# schematic.net
KiCad netlist of a schematic drawn in EAGLE
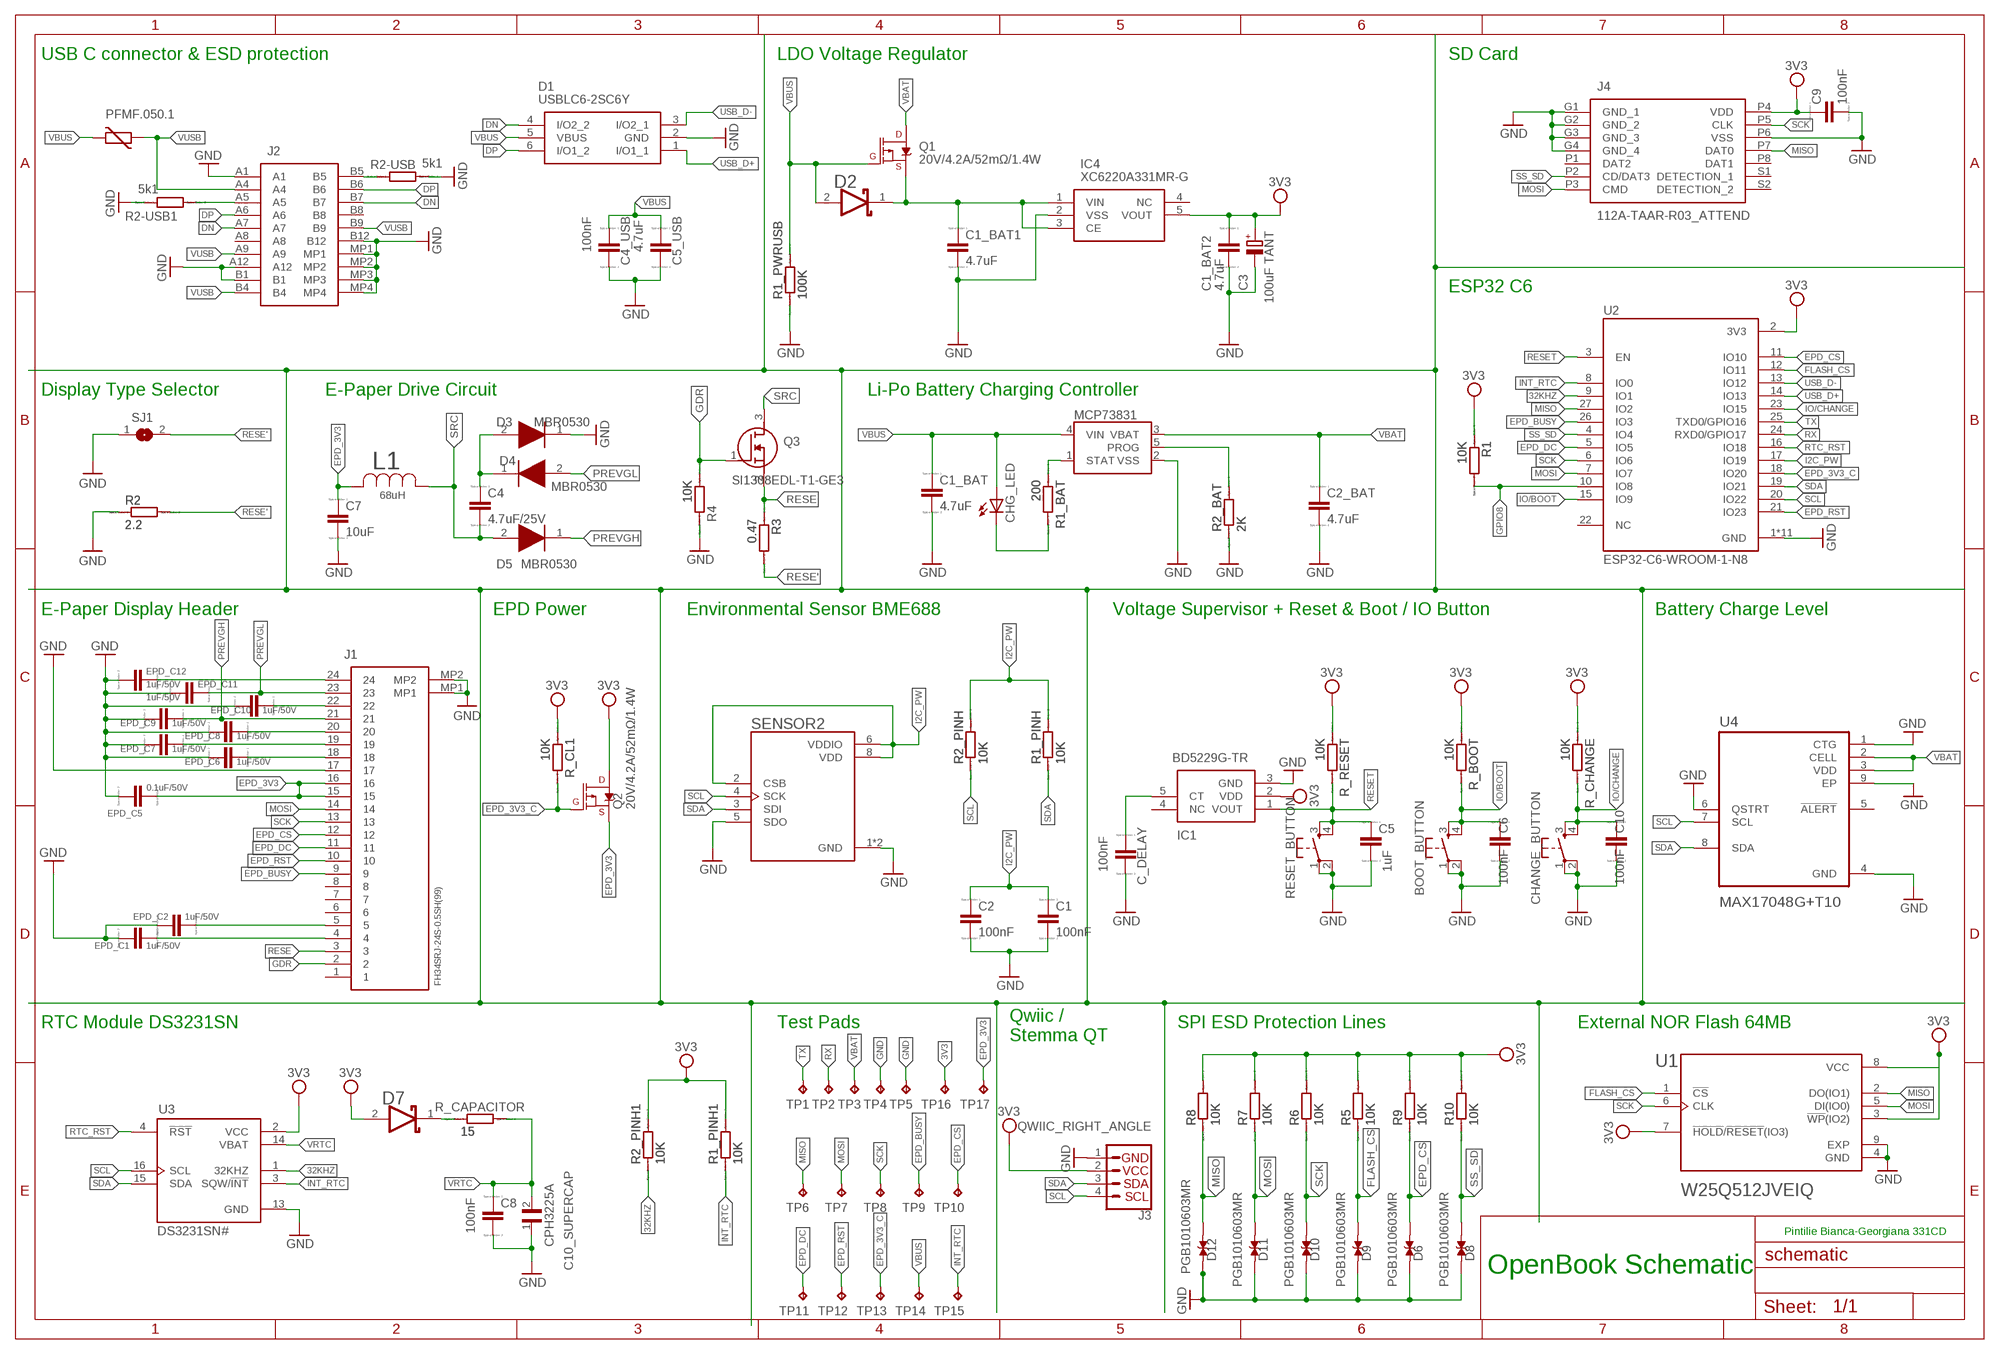
[diagram p0: schematic, sheet 1]

(export (version "E")
  (design (tool "Eeschema 10.0.6"))
  (components
    (comp (ref "BOOT_BUTTON")
      (value "BUTTON_CUSYOMV1")
      (footprint "eagle-import:MYBUTTON")
      (libsource (lib "eagle-import") (part "BUTTON_CUSYOMV1"))
    )
    (comp (ref "C1")
      (value "100nF")
      (footprint "eagle-import:EAGLE-LTSPICE_C0402")
      (libsource (lib "eagle-import") (part "EAGLE-LTSPICE_CC0402"))
    )
    (comp (ref "C1_BAT")
      (value "4.7uF")
      (footprint "eagle-import:EAGLE-LTSPICE_C0402")
      (libsource (lib "eagle-import") (part "EAGLE-LTSPICE_CC0402"))
    )
    (comp (ref "C1_BAT1")
      (value "4.7uF")
      (footprint "eagle-import:EAGLE-LTSPICE_C0402")
      (libsource (lib "eagle-import") (part "EAGLE-LTSPICE_CC0402"))
    )
    (comp (ref "C1_BAT2")
      (value "4.7uF")
      (footprint "eagle-import:EAGLE-LTSPICE_C0402")
      (libsource (lib "eagle-import") (part "EAGLE-LTSPICE_CC0402"))
    )
    (comp (ref "C2")
      (value "100nF")
      (footprint "eagle-import:EAGLE-LTSPICE_C0402")
      (libsource (lib "eagle-import") (part "EAGLE-LTSPICE_CC0402"))
    )
    (comp (ref "C2_BAT")
      (value "4.7uF")
      (footprint "eagle-import:EAGLE-LTSPICE_C0402")
      (libsource (lib "eagle-import") (part "EAGLE-LTSPICE_CC0402"))
    )
    (comp (ref "C3")
      (value "100uF TANT")
      (footprint "eagle-import:RCL_CT3528")
      (libsource (lib "eagle-import") (part "RCL_CPOL-EUCT3528"))
    )
    (comp (ref "C4")
      (value "4.7uF/25V")
      (footprint "eagle-import:EAGLE-LTSPICE_C0402")
      (libsource (lib "eagle-import") (part "EAGLE-LTSPICE_CC0402"))
    )
    (comp (ref "C4_USB")
      (value "100nF")
      (footprint "eagle-import:EAGLE-LTSPICE_C0402")
      (libsource (lib "eagle-import") (part "EAGLE-LTSPICE_CC0402"))
    )
    (comp (ref "C5")
      (value "1uF")
      (footprint "eagle-import:EAGLE-LTSPICE_C0402")
      (libsource (lib "eagle-import") (part "EAGLE-LTSPICE_CC0402"))
    )
    (comp (ref "C5_USB")
      (value "4.7uF")
      (footprint "eagle-import:EAGLE-LTSPICE_C0402")
      (libsource (lib "eagle-import") (part "EAGLE-LTSPICE_CC0402"))
    )
    (comp (ref "C6")
      (value "100nF")
      (footprint "eagle-import:EAGLE-LTSPICE_C0402")
      (libsource (lib "eagle-import") (part "EAGLE-LTSPICE_CC0402"))
    )
    (comp (ref "C7")
      (value "10uF")
      (footprint "eagle-import:EAGLE-LTSPICE_C0402")
      (libsource (lib "eagle-import") (part "EAGLE-LTSPICE_CC0402"))
    )
    (comp (ref "C8")
      (value "100nF")
      (footprint "eagle-import:EAGLE-LTSPICE_C0402")
      (libsource (lib "eagle-import") (part "EAGLE-LTSPICE_CC0402"))
    )
    (comp (ref "C9")
      (value "100nF")
      (footprint "eagle-import:EAGLE-LTSPICE_C0402")
      (libsource (lib "eagle-import") (part "EAGLE-LTSPICE_CC0402"))
    )
    (comp (ref "C10")
      (value "100nF")
      (footprint "eagle-import:EAGLE-LTSPICE_C0402")
      (libsource (lib "eagle-import") (part "EAGLE-LTSPICE_CC0402"))
    )
    (comp (ref "C10_SUPERCAP")
      (value "CPH3225A")
      (footprint "eagle-import:CAPCP3225X100N")
      (fields (field (name "MF") "Seiko Instruments"))
      (libsource (lib "eagle-import") (part "CPH3225A"))
    )
    (comp (ref "CHANGE_BUTTON")
      (value "BUTTON_CUSYOMV1")
      (footprint "eagle-import:MYBUTTON")
      (libsource (lib "eagle-import") (part "BUTTON_CUSYOMV1"))
    )
    (comp (ref "CHG_LED")
      (value "ADAFRUIT_LEDCHIP-LED0603")
      (footprint "eagle-import:ADAFRUIT_CHIP-LED0603")
      (libsource (lib "eagle-import") (part "ADAFRUIT_LEDCHIP-LED0603"))
    )
    (comp (ref "C_DELAY")
      (value "100nF")
      (footprint "eagle-import:EAGLE-LTSPICE_C0402")
      (libsource (lib "eagle-import") (part "EAGLE-LTSPICE_CC0402"))
    )
    (comp (ref "D1")
      (value "USBLC6-2SC6Y")
      (footprint "eagle-import:SOT95P280X145-6N")
      (fields (field (name "MF") "STMicroelectronics"))
      (libsource (lib "eagle-import") (part "USBLC6-2SC6Y"))
    )
    (comp (ref "D2")
      (value "ESP32_WROVER_AVX---SD0805S020S1R0_AVX_SD0805S020S1R0_0_0AVX_SD0805S020S1R0_0_0")
      (footprint "eagle-import:ESP32_WROVER_AVX---SD0805S020S1R0_AVX_SD0805S020S1R0_0")
      (fields
        (field (name "DIGIKEY_PART_NUMBER") "478-7800-1-ND")
        (field (name "MF") "AVX")
        (field (name "MOUSER_PART_NUMBER") "581-SD0805S020S1R0")
      )
      (libsource (lib "eagle-import") (part "ESP32_WROVER_AVX---SD0805S020S1R0_AVX_SD0805S020S1R0_0_0AVX_SD0805S020S1R0_0_0"))
    )
    (comp (ref "D3")
      (value "MBR0530")
      (footprint "eagle-import:SOD3716X135N")
      (fields (field (name "MF") "ON Semiconductor"))
      (libsource (lib "eagle-import") (part "MBR0530"))
    )
    (comp (ref "D4")
      (value "MBR0530")
      (footprint "eagle-import:SOD3716X135N")
      (fields (field (name "MF") "ON Semiconductor"))
      (libsource (lib "eagle-import") (part "MBR0530"))
    )
    (comp (ref "D5")
      (value "MBR0530")
      (footprint "eagle-import:SOD3716X135N")
      (fields (field (name "MF") "ON Semiconductor"))
      (libsource (lib "eagle-import") (part "MBR0530"))
    )
    (comp (ref "D6")
      (value "PGB1010603MR")
      (footprint "eagle-import:DIOC1608X36N")
      (fields (field (name "MF") "Littelfuse Inc."))
      (libsource (lib "eagle-import") (part "PGB1010603MR"))
    )
    (comp (ref "D7")
      (value "ESP32_WROVER_AVX---SD0805S020S1R0_AVX_SD0805S020S1R0_0_0AVX_SD0805S020S1R0_0_0")
      (footprint "eagle-import:ESP32_WROVER_AVX---SD0805S020S1R0_AVX_SD0805S020S1R0_0")
      (fields
        (field (name "DIGIKEY_PART_NUMBER") "478-7800-1-ND")
        (field (name "MF") "AVX")
        (field (name "MOUSER_PART_NUMBER") "581-SD0805S020S1R0")
      )
      (libsource (lib "eagle-import") (part "ESP32_WROVER_AVX---SD0805S020S1R0_AVX_SD0805S020S1R0_0_0AVX_SD0805S020S1R0_0_0"))
    )
    (comp (ref "D8")
      (value "PGB1010603MR")
      (footprint "eagle-import:DIOC1608X36N")
      (fields (field (name "MF") "Littelfuse Inc."))
      (libsource (lib "eagle-import") (part "PGB1010603MR"))
    )
    (comp (ref "D9")
      (value "PGB1010603MR")
      (footprint "eagle-import:DIOC1608X36N")
      (fields (field (name "MF") "Littelfuse Inc."))
      (libsource (lib "eagle-import") (part "PGB1010603MR"))
    )
    (comp (ref "D10")
      (value "PGB1010603MR")
      (footprint "eagle-import:DIOC1608X36N")
      (fields (field (name "MF") "Littelfuse Inc."))
      (libsource (lib "eagle-import") (part "PGB1010603MR"))
    )
    (comp (ref "D11")
      (value "PGB1010603MR")
      (footprint "eagle-import:DIOC1608X36N")
      (fields (field (name "MF") "Littelfuse Inc."))
      (libsource (lib "eagle-import") (part "PGB1010603MR"))
    )
    (comp (ref "D12")
      (value "PGB1010603MR")
      (footprint "eagle-import:DIOC1608X36N")
      (fields (field (name "MF") "Littelfuse Inc."))
      (libsource (lib "eagle-import") (part "PGB1010603MR"))
    )
    (comp (ref "EPD_C1")
      (value "1uF/50V")
      (footprint "eagle-import:ESP32_WROVER_EAGLE-LTSPICE_C0402")
      (libsource (lib "eagle-import") (part "ESP32_WROVER_EAGLE-LTSPICE_CC0402"))
    )
    (comp (ref "EPD_C2")
      (value "1uF/50V")
      (footprint "eagle-import:ESP32_WROVER_EAGLE-LTSPICE_C0402")
      (libsource (lib "eagle-import") (part "ESP32_WROVER_EAGLE-LTSPICE_CC0402"))
    )
    (comp (ref "EPD_C5")
      (value "0.1uF/50V")
      (footprint "eagle-import:ESP32_WROVER_EAGLE-LTSPICE_C0402")
      (libsource (lib "eagle-import") (part "ESP32_WROVER_EAGLE-LTSPICE_CC0402"))
    )
    (comp (ref "EPD_C6")
      (value "1uF/50V")
      (footprint "eagle-import:ESP32_WROVER_EAGLE-LTSPICE_C0402")
      (libsource (lib "eagle-import") (part "ESP32_WROVER_EAGLE-LTSPICE_CC0402"))
    )
    (comp (ref "EPD_C7")
      (value "1uF/50V")
      (footprint "eagle-import:ESP32_WROVER_EAGLE-LTSPICE_C0402")
      (libsource (lib "eagle-import") (part "ESP32_WROVER_EAGLE-LTSPICE_CC0402"))
    )
    (comp (ref "EPD_C8")
      (value "1uF/50V")
      (footprint "eagle-import:ESP32_WROVER_EAGLE-LTSPICE_C0402")
      (libsource (lib "eagle-import") (part "ESP32_WROVER_EAGLE-LTSPICE_CC0402"))
    )
    (comp (ref "EPD_C9")
      (value "1uF/50V")
      (footprint "eagle-import:ESP32_WROVER_EAGLE-LTSPICE_C0402")
      (libsource (lib "eagle-import") (part "ESP32_WROVER_EAGLE-LTSPICE_CC0402"))
    )
    (comp (ref "EPD_C10")
      (value "1uF/50V")
      (footprint "eagle-import:ESP32_WROVER_EAGLE-LTSPICE_C0402")
      (fields (field (name "SPICEPREFIX") "EPD_C10"))
      (libsource (lib "eagle-import") (part "ESP32_WROVER_EAGLE-LTSPICE_CC0402"))
    )
    (comp (ref "EPD_C11")
      (value "1uF/50V")
      (footprint "eagle-import:ESP32_WROVER_EAGLE-LTSPICE_C0402")
      (libsource (lib "eagle-import") (part "ESP32_WROVER_EAGLE-LTSPICE_CC0402"))
    )
    (comp (ref "EPD_C12")
      (value "1uF/50V")
      (footprint "eagle-import:ESP32_WROVER_EAGLE-LTSPICE_C0402")
      (libsource (lib "eagle-import") (part "ESP32_WROVER_EAGLE-LTSPICE_CC0402"))
    )
    (comp (ref "IC1")
      (value "BD5229G-TR")
      (footprint "eagle-import:SOT95P280X125-5N")
      (fields (field (name "MOUSER_PART_NUMBER") "755-BD5229G-TR"))
      (libsource (lib "eagle-import") (part "BD5229G-TR"))
    )
    (comp (ref "IC4")
      (value "XC6220A331MR-G")
      (footprint "eagle-import:SOT95P280X120-5N")
      (fields (field (name "MOUSER_PART_NUMBER") "865-XC6220A331MR-G"))
      (libsource (lib "eagle-import") (part "XC6220A331MR-G"))
    )
    (comp (ref "J1")
      (value "FH34SRJ-24S-0.5SH_99_")
      (footprint "eagle-import:FH34SRJ24S05SH99")
      (fields
        (field (name "MANUFACTURER_PART_NUMBER") "FH34SRJ-24S-0.5SH(99)")
        (field (name "MOUSER_PART_NUMBER") "798-FH34SRJ24S05SH99")
      )
      (libsource (lib "eagle-import") (part "FH34SRJ-24S-0.5SH_99_"))
    )
    (comp (ref "J2")
      (value "SAMACSYS_PARTS_USB4110-GF-A")
      (footprint "eagle-import:SAMACSYS_PARTS_USB4110GFA")
      (fields
        (field (name "MANUFACTURER_PART_NUMBER") "USB4110-GF-A")
        (field (name "MOUSER_PART_NUMBER") "640-USB4110-GF-A")
      )
      (libsource (lib "eagle-import") (part "SAMACSYS_PARTS_USB4110-GF-A"))
    )
    (comp (ref "J3")
      (value "QWIIC_RIGHT_ANGLE")
      (footprint "eagle-import:JST04_1MM_RA")
      (libsource (lib "eagle-import") (part "QWIIC_CONNECTORJS-1MM"))
    )
    (comp (ref "J4")
      (value "112A-TAAR-R03_ATTEND")
      (footprint "eagle-import:112ATAARR03ATTEND")
      (fields (field (name "MANUFACTURER_PART_NUMBER") "112A-TAAR-R03 ATTEND"))
      (libsource (lib "eagle-import") (part "112A-TAAR-R03_ATTEND"))
    )
    (comp (ref "L1")
      (value "68uH")
      (footprint "eagle-import:IND_4828-WE-TPC_WRE")
      (fields
        (field (name "MANUFACTURER_PART_NUMBER") "744043680")
        (field (name "COPYRIGHT") "Copyright (C) 2024 Ultra Librarian. All rights reserved.")
      )
      (libsource (lib "eagle-import") (part "744043680IND_4828-WE-TPC_WRE"))
    )
    (comp (ref "MCP73831")
      (value "ESP32_WROVER_SPARKFUN-IC-POWER_MCP73831")
      (footprint "eagle-import:ESP32_WROVER_SPARKFUN-IC-POWER_SOT23-5")
      (libsource (lib "eagle-import") (part "ESP32_WROVER_SPARKFUN-IC-POWER_MCP73831"))
    )
    (comp (ref "PFMF.050.1")
      (value "ESP32C6_VARISTORCN1812")
      (footprint "eagle-import:ESP32C6_VARISTOR_CT_CN1812")
      (libsource (lib "eagle-import") (part "ESP32C6_VARISTORCN1812"))
    )
    (comp (ref "Q1")
      (value "20V/4.2A/52mΩ/1.4W")
      (footprint "eagle-import:ESP32_WROVER_SPARKFUN-DISCRETESEMI_SOT23-3")
      (libsource (lib "eagle-import") (part "ESP32_WROVER_SPARKFUN-DISCRETESEMI_MOSFET_PCH-DMG2305UX-7"))
    )
    (comp (ref "Q2")
      (value "20V/4.2A/52mΩ/1.4W")
      (footprint "eagle-import:ESP32_WROVER_SPARKFUN-DISCRETESEMI_SOT23-3")
      (libsource (lib "eagle-import") (part "ESP32_WROVER_SPARKFUN-DISCRETESEMI_MOSFET_PCH-DMG2305UX-7"))
    )
    (comp (ref "Q3")
      (value "SI1308EDL-T1-GE3")
      (footprint "eagle-import:SOT65P210X110-3N")
      (fields (field (name "MF") "Vishay Siliconix"))
      (libsource (lib "eagle-import") (part "SI1308EDL-T1-GE3"))
    )
    (comp (ref "R1")
      (value "10K")
      (footprint "eagle-import:ESP32_WROVER_EAGLE-LTSPICE_R0402")
      (libsource (lib "eagle-import") (part "ESP32_WROVER_EAGLE-LTSPICE_RR0402"))
    )
    (comp (ref "R1_BAT")
      (value "200")
      (footprint "eagle-import:ESP32_WROVER_EAGLE-LTSPICE_R0402")
      (libsource (lib "eagle-import") (part "ESP32_WROVER_EAGLE-LTSPICE_RR0402"))
    )
    (comp (ref "R1_PINH")
      (value "10K")
      (footprint "eagle-import:ESP32_WROVER_EAGLE-LTSPICE_R0402")
      (libsource (lib "eagle-import") (part "ESP32_WROVER_EAGLE-LTSPICE_RR0402"))
    )
    (comp (ref "R1_PINH1")
      (value "10K")
      (footprint "eagle-import:ESP32_WROVER_EAGLE-LTSPICE_R0402")
      (libsource (lib "eagle-import") (part "ESP32_WROVER_EAGLE-LTSPICE_RR0402"))
    )
    (comp (ref "R1_PWRUSB")
      (value "100K")
      (footprint "eagle-import:ESP32_WROVER_EAGLE-LTSPICE_R0402")
      (libsource (lib "eagle-import") (part "ESP32_WROVER_EAGLE-LTSPICE_RR0402"))
    )
    (comp (ref "R2")
      (value "2.2")
      (footprint "eagle-import:ESP32_WROVER_EAGLE-LTSPICE_R0402")
      (libsource (lib "eagle-import") (part "ESP32_WROVER_EAGLE-LTSPICE_RR0402"))
    )
    (comp (ref "R2-USB")
      (value "5k1")
      (footprint "eagle-import:ESP32_WROVER_EAGLE-LTSPICE_R0402")
      (libsource (lib "eagle-import") (part "ESP32_WROVER_EAGLE-LTSPICE_RR0402"))
    )
    (comp (ref "R2-USB1")
      (value "5k1")
      (footprint "eagle-import:ESP32_WROVER_EAGLE-LTSPICE_R0402")
      (libsource (lib "eagle-import") (part "ESP32_WROVER_EAGLE-LTSPICE_RR0402"))
    )
    (comp (ref "R2_BAT")
      (value "2K")
      (footprint "eagle-import:ESP32_WROVER_EAGLE-LTSPICE_R0402")
      (libsource (lib "eagle-import") (part "ESP32_WROVER_EAGLE-LTSPICE_RR0402"))
    )
    (comp (ref "R2_PINH")
      (value "10K")
      (footprint "eagle-import:ESP32_WROVER_EAGLE-LTSPICE_R0402")
      (libsource (lib "eagle-import") (part "ESP32_WROVER_EAGLE-LTSPICE_RR0402"))
    )
    (comp (ref "R2_PINH1")
      (value "10K")
      (footprint "eagle-import:ESP32_WROVER_EAGLE-LTSPICE_R0402")
      (libsource (lib "eagle-import") (part "ESP32_WROVER_EAGLE-LTSPICE_RR0402"))
    )
    (comp (ref "R3")
      (value "0.47")
      (footprint "eagle-import:ESP32_WROVER_EAGLE-LTSPICE_R0402")
      (libsource (lib "eagle-import") (part "ESP32_WROVER_EAGLE-LTSPICE_RR0402"))
    )
    (comp (ref "R4")
      (value "10K")
      (footprint "eagle-import:ESP32_WROVER_EAGLE-LTSPICE_R0402")
      (libsource (lib "eagle-import") (part "ESP32_WROVER_EAGLE-LTSPICE_RR0402"))
    )
    (comp (ref "R5")
      (value "10K")
      (footprint "eagle-import:ESP32_WROVER_EAGLE-LTSPICE_R0402")
      (libsource (lib "eagle-import") (part "ESP32_WROVER_EAGLE-LTSPICE_RR0402"))
    )
    (comp (ref "R6")
      (value "10K")
      (footprint "eagle-import:ESP32_WROVER_EAGLE-LTSPICE_R0402")
      (libsource (lib "eagle-import") (part "ESP32_WROVER_EAGLE-LTSPICE_RR0402"))
    )
    (comp (ref "R7")
      (value "10K")
      (footprint "eagle-import:ESP32_WROVER_EAGLE-LTSPICE_R0402")
      (libsource (lib "eagle-import") (part "ESP32_WROVER_EAGLE-LTSPICE_RR0402"))
    )
    (comp (ref "R8")
      (value "10K")
      (footprint "eagle-import:ESP32_WROVER_EAGLE-LTSPICE_R0402")
      (libsource (lib "eagle-import") (part "ESP32_WROVER_EAGLE-LTSPICE_RR0402"))
    )
    (comp (ref "R9")
      (value "10K")
      (footprint "eagle-import:ESP32_WROVER_EAGLE-LTSPICE_R0402")
      (libsource (lib "eagle-import") (part "ESP32_WROVER_EAGLE-LTSPICE_RR0402"))
    )
    (comp (ref "R10")
      (value "10K")
      (footprint "eagle-import:ESP32_WROVER_EAGLE-LTSPICE_R0402")
      (libsource (lib "eagle-import") (part "ESP32_WROVER_EAGLE-LTSPICE_RR0402"))
    )
    (comp (ref "RESET_BUTTON")
      (value "BUTTON_CUSYOMV1")
      (footprint "eagle-import:MYBUTTON")
      (libsource (lib "eagle-import") (part "BUTTON_CUSYOMV1"))
    )
    (comp (ref "R_BOOT")
      (value "10K")
      (footprint "eagle-import:ESP32_WROVER_EAGLE-LTSPICE_R0402")
      (libsource (lib "eagle-import") (part "ESP32_WROVER_EAGLE-LTSPICE_RR0402"))
    )
    (comp (ref "R_CAPACITOR")
      (value "15")
      (footprint "eagle-import:ESP32_WROVER_EAGLE-LTSPICE_R0402")
      (libsource (lib "eagle-import") (part "ESP32_WROVER_EAGLE-LTSPICE_RR0402"))
    )
    (comp (ref "R_CHANGE")
      (value "10K")
      (footprint "eagle-import:ESP32_WROVER_EAGLE-LTSPICE_R0402")
      (libsource (lib "eagle-import") (part "ESP32_WROVER_EAGLE-LTSPICE_RR0402"))
    )
    (comp (ref "R_CL1")
      (value "10K")
      (footprint "eagle-import:ESP32_WROVER_EAGLE-LTSPICE_R0402")
      (libsource (lib "eagle-import") (part "ESP32_WROVER_EAGLE-LTSPICE_RR0402"))
    )
    (comp (ref "R_RESET")
      (value "10K")
      (footprint "eagle-import:ESP32_WROVER_EAGLE-LTSPICE_R0402")
      (libsource (lib "eagle-import") (part "ESP32_WROVER_EAGLE-LTSPICE_RR0402"))
    )
    (comp (ref "SENSOR2")
      (value "ESP32_WROVER_BME680_BME680")
      (footprint "eagle-import:ESP32_WROVER_BME680_PSON80P300X300X100-8N")
      (fields (field (name "MF") "Bosch Sensortec") (field (name "MP") "BME680"))
      (libsource (lib "eagle-import") (part "ESP32_WROVER_BME680_BME680"))
    )
    (comp (ref "SJ1") (value "SJ") (footprint "eagle-import:SJ") (libsource (lib "eagle-import") (part "SJ")))
    (comp (ref "TP1")
      (value "TPTP20R")
      (footprint "eagle-import:TP20R")
      (libsource (lib "eagle-import") (part "TPTP20R"))
    )
    (comp (ref "TP2")
      (value "TPTP20R")
      (footprint "eagle-import:TP20R")
      (libsource (lib "eagle-import") (part "TPTP20R"))
    )
    (comp (ref "TP3")
      (value "TPTP20R")
      (footprint "eagle-import:TP20R")
      (libsource (lib "eagle-import") (part "TPTP20R"))
    )
    (comp (ref "TP4")
      (value "TPTP20R")
      (footprint "eagle-import:TP20R")
      (libsource (lib "eagle-import") (part "TPTP20R"))
    )
    (comp (ref "TP5")
      (value "TPTP20R")
      (footprint "eagle-import:TP20R")
      (libsource (lib "eagle-import") (part "TPTP20R"))
    )
    (comp (ref "TP6")
      (value "TPTP20R")
      (footprint "eagle-import:TP20R")
      (libsource (lib "eagle-import") (part "TPTP20R"))
    )
    (comp (ref "TP7")
      (value "TPTP20R")
      (footprint "eagle-import:TP20R")
      (libsource (lib "eagle-import") (part "TPTP20R"))
    )
    (comp (ref "TP8")
      (value "TPTP20R")
      (footprint "eagle-import:TP20R")
      (libsource (lib "eagle-import") (part "TPTP20R"))
    )
    (comp (ref "TP9")
      (value "TPTP20R")
      (footprint "eagle-import:TP20R")
      (libsource (lib "eagle-import") (part "TPTP20R"))
    )
    (comp (ref "TP10")
      (value "TPTP20R")
      (footprint "eagle-import:TP20R")
      (libsource (lib "eagle-import") (part "TPTP20R"))
    )
    (comp (ref "TP11")
      (value "TPTP20R")
      (footprint "eagle-import:TP20R")
      (libsource (lib "eagle-import") (part "TPTP20R"))
    )
    (comp (ref "TP12")
      (value "TPTP20R")
      (footprint "eagle-import:TP20R")
      (libsource (lib "eagle-import") (part "TPTP20R"))
    )
    (comp (ref "TP13")
      (value "TPTP20R")
      (footprint "eagle-import:TP20R")
      (libsource (lib "eagle-import") (part "TPTP20R"))
    )
    (comp (ref "TP14")
      (value "TPTP20R")
      (footprint "eagle-import:TP20R")
      (libsource (lib "eagle-import") (part "TPTP20R"))
    )
    (comp (ref "TP15")
      (value "TPTP20R")
      (footprint "eagle-import:TP20R")
      (libsource (lib "eagle-import") (part "TPTP20R"))
    )
    (comp (ref "TP16")
      (value "TPTP20R")
      (footprint "eagle-import:TP20R")
      (libsource (lib "eagle-import") (part "TPTP20R"))
    )
    (comp (ref "TP17")
      (value "TPTP20R")
      (footprint "eagle-import:TP20R")
      (libsource (lib "eagle-import") (part "TPTP20R"))
    )
    (comp (ref "U1")
      (value "W25Q512JVEIQ")
      (footprint "eagle-import:SON127P600X800X80-9N")
      (fields (field (name "MF") "Winbond Electronics"))
      (libsource (lib "eagle-import") (part "W25Q512JVEIQ"))
    )
    (comp (ref "U2")
      (value "ESP32-C6-WROOM-1-N8")
      (footprint "eagle-import:XCVR_ESP32-C6-WROOM-1-N8")
      (fields (field (name "MF") "Espressif Systems"))
      (libsource (lib "eagle-import") (part "ESP32-C6-WROOM-1-N8"))
    )
    (comp (ref "U3")
      (value "DS3231SN#")
      (footprint "eagle-import:SOIC127P1032X265-16N")
      (fields (field (name "MF") "Analog Devices"))
      (libsource (lib "eagle-import") (part "DS3231SN#"))
    )
    (comp (ref "U4")
      (value "MAX17048G+T10")
      (footprint "eagle-import:SON50P200X200X80-9N")
      (fields (field (name "MF") "Analog Devices"))
      (libsource (lib "eagle-import") (part "MAX17048G+T10"))
    )
  )
  (nets
    (net (code "1") (name "3V3") (class "Default")
      (node (ref "C1_BAT2") (pin "1") (pinfunction "1_1") (pintype "passive"))
      (node (ref "C3") (pin "+") (pinfunction "+_+") (pintype "passive"))
      (node (ref "C9") (pin "1") (pinfunction "1_1") (pintype "passive"))
      (node (ref "D7") (pin "2") (pinfunction "ANODE_2") (pintype "bidirectional"))
      (node (ref "IC1") (pin "2") (pinfunction "VDD_2") (pintype "bidirectional"))
      (node (ref "IC4") (pin "5") (pinfunction "VOUT_5") (pintype "bidirectional"))
      (node (ref "J3") (pin "2") (pinfunction "2_2") (pintype "power_in"))
      (node (ref "J4") (pin "P4") (pinfunction "VDD_P4") (pintype "bidirectional"))
      (node (ref "Q2") (pin "3") (pinfunction "D_3") (pintype "bidirectional"))
      (node (ref "R1") (pin "1") (pinfunction "1_1") (pintype "passive"))
      (node (ref "R10") (pin "2") (pinfunction "2_2") (pintype "passive"))
      (node (ref "R1_PINH1") (pin "2") (pinfunction "2_2") (pintype "passive"))
      (node (ref "R2_PINH1") (pin "2") (pinfunction "2_2") (pintype "passive"))
      (node (ref "R5") (pin "2") (pinfunction "2_2") (pintype "passive"))
      (node (ref "R6") (pin "2") (pinfunction "2_2") (pintype "passive"))
      (node (ref "R7") (pin "2") (pinfunction "2_2") (pintype "passive"))
      (node (ref "R8") (pin "2") (pinfunction "2_2") (pintype "passive"))
      (node (ref "R9") (pin "2") (pinfunction "2_2") (pintype "passive"))
      (node (ref "R_BOOT") (pin "1") (pinfunction "1_1") (pintype "passive"))
      (node (ref "R_CHANGE") (pin "1") (pinfunction "1_1") (pintype "passive"))
      (node (ref "R_CL1") (pin "1") (pinfunction "1_1") (pintype "passive"))
      (node (ref "R_RESET") (pin "1") (pinfunction "1_1") (pintype "passive"))
      (node (ref "TP16") (pin "TP") (pinfunction "TP_TP") (pintype "input"))
      (node (ref "U1") (pin "3") (pinfunction "~{WP}(IO2)_3") (pintype "bidirectional"))
      (node (ref "U1") (pin "7") (pinfunction "~{HOLD}/~{RESET}(IO3)_7") (pintype "bidirectional"))
      (node (ref "U1") (pin "8") (pinfunction "VCC_8") (pintype "power_in"))
      (node (ref "U2") (pin "2") (pinfunction "3V3_2") (pintype "power_in"))
      (node (ref "U3") (pin "2") (pinfunction "VCC_2") (pintype "power_in"))
    )
    (net (code "2") (name "32KHZ") (class "Default")
      (node (ref "R2_PINH1") (pin "1") (pinfunction "1_1") (pintype "passive"))
      (node (ref "U2") (pin "9") (pinfunction "IO1_9") (pintype "bidirectional"))
      (node (ref "U3") (pin "1") (pinfunction "32KHZ_1") (pintype "output"))
    )
    (net (code "3") (name "DN") (class "Default")
      (node (ref "D1") (pin "4") (pinfunction "I/O2_2_4") (pintype "bidirectional"))
      (node (ref "J2") (pin "A7") (pinfunction "A7_A7") (pintype "bidirectional"))
      (node (ref "J2") (pin "B7") (pinfunction "B7_B7") (pintype "bidirectional"))
    )
    (net (code "4") (name "DP") (class "Default")
      (node (ref "D1") (pin "6") (pinfunction "I/O1_2_6") (pintype "bidirectional"))
      (node (ref "J2") (pin "A6") (pinfunction "A6_A6") (pintype "bidirectional"))
      (node (ref "J2") (pin "B6") (pinfunction "B6_B6") (pintype "bidirectional"))
    )
    (net (code "5") (name "EPD_3V3") (class "Default")
      (node (ref "C7") (pin "1") (pinfunction "1_1") (pintype "passive"))
      (node (ref "EPD_C5") (pin "1") (pinfunction "1_1") (pintype "passive"))
      (node (ref "J1") (pin "15") (pinfunction "15_15") (pintype "bidirectional"))
      (node (ref "J1") (pin "16") (pinfunction "16_16") (pintype "bidirectional"))
      (node (ref "L1") (pin "2") (pinfunction "2_2") (pintype "passive"))
      (node (ref "Q2") (pin "2") (pinfunction "S_2") (pintype "bidirectional"))
      (node (ref "TP17") (pin "TP") (pinfunction "TP_TP") (pintype "input"))
    )
    (net (code "6") (name "EPD_3V3_C") (class "Default")
      (node (ref "Q2") (pin "1") (pinfunction "G_1") (pintype "bidirectional"))
      (node (ref "R_CL1") (pin "2") (pinfunction "2_2") (pintype "passive"))
      (node (ref "TP13") (pin "TP") (pinfunction "TP_TP") (pintype "input"))
      (node (ref "U2") (pin "18") (pinfunction "IO20_18") (pintype "bidirectional"))
    )
    (net (code "7") (name "EPD_BUSY") (class "Default")
      (node (ref "J1") (pin "9") (pinfunction "9_9") (pintype "bidirectional"))
      (node (ref "TP9") (pin "TP") (pinfunction "TP_TP") (pintype "input"))
      (node (ref "U2") (pin "26") (pinfunction "IO3_26") (pintype "bidirectional"))
    )
    (net (code "8") (name "EPD_CS") (class "Default")
      (node (ref "D6") (pin "2") (pinfunction "2_2") (pintype "passive"))
      (node (ref "J1") (pin "12") (pinfunction "12_12") (pintype "bidirectional"))
      (node (ref "R9") (pin "1") (pinfunction "1_1") (pintype "passive"))
      (node (ref "TP10") (pin "TP") (pinfunction "TP_TP") (pintype "input"))
      (node (ref "U2") (pin "11") (pinfunction "IO10_11") (pintype "bidirectional"))
    )
    (net (code "9") (name "EPD_DC") (class "Default")
      (node (ref "J1") (pin "11") (pinfunction "11_11") (pintype "bidirectional"))
      (node (ref "TP11") (pin "TP") (pinfunction "TP_TP") (pintype "input"))
      (node (ref "U2") (pin "5") (pinfunction "IO5_5") (pintype "bidirectional"))
    )
    (net (code "10") (name "EPD_RST") (class "Default")
      (node (ref "J1") (pin "10") (pinfunction "10_10") (pintype "bidirectional"))
      (node (ref "TP12") (pin "TP") (pinfunction "TP_TP") (pintype "input"))
      (node (ref "U2") (pin "21") (pinfunction "IO23_21") (pintype "bidirectional"))
    )
    (net (code "11") (name "FLASH_CS") (class "Default")
      (node (ref "D9") (pin "2") (pinfunction "2_2") (pintype "passive"))
      (node (ref "R5") (pin "1") (pinfunction "1_1") (pintype "passive"))
      (node (ref "U1") (pin "1") (pinfunction "~{CS}_1") (pintype "input"))
      (node (ref "U2") (pin "12") (pinfunction "IO11_12") (pintype "bidirectional"))
    )
    (net (code "12") (name "GDR") (class "Default")
      (node (ref "J1") (pin "2") (pinfunction "2_2") (pintype "bidirectional"))
      (node (ref "Q3") (pin "1") (pinfunction "G_1") (pintype "bidirectional"))
      (node (ref "R4") (pin "1") (pinfunction "1_1") (pintype "passive"))
    )
    (net (code "13") (name "GND") (class "Default")
      (node (ref "BOOT_BUTTON") (pin "1") (pinfunction "1_1") (pintype "passive"))
      (node (ref "BOOT_BUTTON") (pin "2") (pinfunction "2_2") (pintype "passive"))
      (node (ref "C1") (pin "2") (pinfunction "2_2") (pintype "passive"))
      (node (ref "C10") (pin "2") (pinfunction "2_2") (pintype "passive"))
      (node (ref "C10_SUPERCAP") (pin "1") (pinfunction "1_1") (pintype "passive"))
      (node (ref "C1_BAT") (pin "2") (pinfunction "2_2") (pintype "passive"))
      (node (ref "C1_BAT1") (pin "2") (pinfunction "2_2") (pintype "passive"))
      (node (ref "C1_BAT2") (pin "2") (pinfunction "2_2") (pintype "passive"))
      (node (ref "C2") (pin "2") (pinfunction "2_2") (pintype "passive"))
      (node (ref "C2_BAT") (pin "2") (pinfunction "2_2") (pintype "passive"))
      (node (ref "C3") (pin "-") (pinfunction "-_-") (pintype "passive"))
      (node (ref "C4_USB") (pin "2") (pinfunction "2_2") (pintype "passive"))
      (node (ref "C5") (pin "2") (pinfunction "2_2") (pintype "passive"))
      (node (ref "C5_USB") (pin "2") (pinfunction "2_2") (pintype "passive"))
      (node (ref "C6") (pin "2") (pinfunction "2_2") (pintype "passive"))
      (node (ref "C7") (pin "2") (pinfunction "2_2") (pintype "passive"))
      (node (ref "C8") (pin "2") (pinfunction "2_2") (pintype "passive"))
      (node (ref "C9") (pin "2") (pinfunction "2_2") (pintype "passive"))
      (node (ref "CHANGE_BUTTON") (pin "1") (pinfunction "1_1") (pintype "passive"))
      (node (ref "CHANGE_BUTTON") (pin "2") (pinfunction "2_2") (pintype "passive"))
      (node (ref "C_DELAY") (pin "2") (pinfunction "2_2") (pintype "passive"))
      (node (ref "D1") (pin "2") (pinfunction "GND_2") (pintype "bidirectional"))
      (node (ref "D10") (pin "1") (pinfunction "1_1") (pintype "passive"))
      (node (ref "D11") (pin "1") (pinfunction "1_1") (pintype "passive"))
      (node (ref "D12") (pin "1") (pinfunction "1_1") (pintype "passive"))
      (node (ref "D3") (pin "1") (pinfunction "K_1") (pintype "bidirectional"))
      (node (ref "D6") (pin "1") (pinfunction "1_1") (pintype "passive"))
      (node (ref "D8") (pin "1") (pinfunction "1_1") (pintype "passive"))
      (node (ref "D9") (pin "1") (pinfunction "1_1") (pintype "passive"))
      (node (ref "EPD_C1") (pin "2") (pinfunction "2_2") (pintype "passive"))
      (node (ref "EPD_C10") (pin "2") (pinfunction "2_2") (pintype "passive"))
      (node (ref "EPD_C11") (pin "2") (pinfunction "2_2") (pintype "passive"))
      (node (ref "EPD_C12") (pin "2") (pinfunction "2_2") (pintype "passive"))
      (node (ref "EPD_C2") (pin "2") (pinfunction "2_2") (pintype "passive"))
      (node (ref "EPD_C5") (pin "2") (pinfunction "2_2") (pintype "passive"))
      (node (ref "EPD_C6") (pin "2") (pinfunction "2_2") (pintype "passive"))
      (node (ref "EPD_C7") (pin "2") (pinfunction "2_2") (pintype "passive"))
      (node (ref "EPD_C8") (pin "2") (pinfunction "2_2") (pintype "passive"))
      (node (ref "EPD_C9") (pin "2") (pinfunction "2_2") (pintype "passive"))
      (node (ref "IC1") (pin "3") (pinfunction "GND_3") (pintype "bidirectional"))
      (node (ref "IC4") (pin "2") (pinfunction "VSS_2") (pintype "bidirectional"))
      (node (ref "J1") (pin "17") (pinfunction "17_17") (pintype "bidirectional"))
      (node (ref "J1") (pin "MP1") (pinfunction "MP1_MP1") (pintype "bidirectional"))
      (node (ref "J1") (pin "MP2") (pinfunction "MP2_MP2") (pintype "bidirectional"))
      (node (ref "J2") (pin "A1") (pinfunction "A1_A1") (pintype "bidirectional"))
      (node (ref "J2") (pin "A12") (pinfunction "A12_A12") (pintype "bidirectional"))
      (node (ref "J2") (pin "B1") (pinfunction "B1_B1") (pintype "bidirectional"))
      (node (ref "J2") (pin "B12") (pinfunction "B12_B12") (pintype "bidirectional"))
      (node (ref "J2") (pin "MP1") (pinfunction "MP1_MP1") (pintype "bidirectional"))
      (node (ref "J2") (pin "MP2") (pinfunction "MP2_MP2") (pintype "bidirectional"))
      (node (ref "J2") (pin "MP3") (pinfunction "MP3_MP3") (pintype "bidirectional"))
      (node (ref "J2") (pin "MP4") (pinfunction "MP4_MP4") (pintype "bidirectional"))
      (node (ref "J3") (pin "1") (pinfunction "1_1") (pintype "power_in"))
      (node (ref "J4") (pin "G1") (pinfunction "GND_1_G1") (pintype "bidirectional"))
      (node (ref "J4") (pin "G2") (pinfunction "GND_2_G2") (pintype "bidirectional"))
      (node (ref "J4") (pin "G3") (pinfunction "GND_3_G3") (pintype "bidirectional"))
      (node (ref "J4") (pin "G4") (pinfunction "GND_4_G4") (pintype "bidirectional"))
      (node (ref "J4") (pin "P6") (pinfunction "VSS_P6") (pintype "bidirectional"))
      (node (ref "MCP73831") (pin "2") (pinfunction "VSS_2") (pintype "power_in"))
      (node (ref "R1_PWRUSB") (pin "1") (pinfunction "1_1") (pintype "passive"))
      (node (ref "R2") (pin "1") (pinfunction "1_1") (pintype "passive"))
      (node (ref "R2-USB") (pin "2") (pinfunction "2_2") (pintype "passive"))
      (node (ref "R2-USB1") (pin "1") (pinfunction "1_1") (pintype "passive"))
      (node (ref "R2_BAT") (pin "1") (pinfunction "1_1") (pintype "passive"))
      (node (ref "R4") (pin "2") (pinfunction "2_2") (pintype "passive"))
      (node (ref "RESET_BUTTON") (pin "1") (pinfunction "1_1") (pintype "passive"))
      (node (ref "RESET_BUTTON") (pin "2") (pinfunction "2_2") (pintype "passive"))
      (node (ref "SENSOR2") (pin "1") (pinfunction "GND_1") (pintype "power_in"))
      (node (ref "SENSOR2") (pin "5") (pinfunction "SDO_5") (pintype "bidirectional"))
      (node (ref "SENSOR2") (pin "7") (pinfunction "GND_7") (pintype "power_in"))
      (node (ref "SJ1") (pin "1") (pinfunction "1_1") (pintype "passive"))
      (node (ref "TP4") (pin "TP") (pinfunction "TP_TP") (pintype "input"))
      (node (ref "TP5") (pin "TP") (pinfunction "TP_TP") (pintype "input"))
      (node (ref "U1") (pin "4") (pinfunction "GND_4") (pintype "power_in"))
      (node (ref "U1") (pin "9") (pinfunction "EXP_9") (pintype "passive"))
      (node (ref "U2") (pin "1") (pinfunction "GND_1") (pintype "power_in"))
      (node (ref "U2") (pin "28") (pinfunction "GND_28") (pintype "power_in"))
      (node (ref "U2") (pin "29_1") (pinfunction "GND_29_1") (pintype "power_in"))
      (node (ref "U2") (pin "29_2") (pinfunction "GND_29_2") (pintype "power_in"))
      (node (ref "U2") (pin "29_3") (pinfunction "GND_29_3") (pintype "power_in"))
      (node (ref "U2") (pin "29_4") (pinfunction "GND_29_4") (pintype "power_in"))
      (node (ref "U2") (pin "29_5") (pinfunction "GND_29_5") (pintype "power_in"))
      (node (ref "U2") (pin "29_6") (pinfunction "GND_29_6") (pintype "power_in"))
      (node (ref "U2") (pin "29_7") (pinfunction "GND_29_7") (pintype "power_in"))
      (node (ref "U2") (pin "29_8") (pinfunction "GND_29_8") (pintype "power_in"))
      (node (ref "U2") (pin "29_9") (pinfunction "GND_29_9") (pintype "power_in"))
      (node (ref "U3") (pin "13") (pinfunction "GND_13") (pintype "power_in"))
      (node (ref "U4") (pin "1") (pinfunction "CTG_1") (pintype "power_in"))
      (node (ref "U4") (pin "4") (pinfunction "GND_4") (pintype "power_in"))
      (node (ref "U4") (pin "6") (pinfunction "QSTRT_6") (pintype "input"))
      (node (ref "U4") (pin "9") (pinfunction "EP_9") (pintype "power_in"))
    )
    (net (code "14") (name "GPIO8") (class "Default")
      (node (ref "R1") (pin "2") (pinfunction "2_2") (pintype "passive"))
      (node (ref "U2") (pin "10") (pinfunction "IO8_10") (pintype "bidirectional"))
    )
    (net (code "15") (name "I2C_PW") (class "Default")
      (node (ref "C1") (pin "1") (pinfunction "1_1") (pintype "passive"))
      (node (ref "C2") (pin "1") (pinfunction "1_1") (pintype "passive"))
      (node (ref "R1_PINH") (pin "2") (pinfunction "2_2") (pintype "passive"))
      (node (ref "R2_PINH") (pin "2") (pinfunction "2_2") (pintype "passive"))
      (node (ref "SENSOR2") (pin "2") (pinfunction "CSB_2") (pintype "input"))
      (node (ref "SENSOR2") (pin "6") (pinfunction "VDDIO_6") (pintype "power_in"))
      (node (ref "SENSOR2") (pin "8") (pinfunction "VDD_8") (pintype "power_in"))
      (node (ref "U2") (pin "17") (pinfunction "IO19_17") (pintype "bidirectional"))
    )
    (net (code "16") (name "INT_RTC") (class "Default")
      (node (ref "R1_PINH1") (pin "1") (pinfunction "1_1") (pintype "passive"))
      (node (ref "TP15") (pin "TP") (pinfunction "TP_TP") (pintype "input"))
      (node (ref "U2") (pin "8") (pinfunction "IO0_8") (pintype "bidirectional"))
      (node (ref "U3") (pin "3") (pinfunction "SQW/~{INT}_3") (pintype "output"))
    )
    (net (code "17") (name "IO{slash}BOOT") (class "Default")
      (node (ref "BOOT_BUTTON") (pin "3") (pinfunction "3_3") (pintype "passive"))
      (node (ref "BOOT_BUTTON") (pin "4") (pinfunction "4_4") (pintype "passive"))
      (node (ref "C6") (pin "1") (pinfunction "1_1") (pintype "passive"))
      (node (ref "R_BOOT") (pin "2") (pinfunction "2_2") (pintype "passive"))
      (node (ref "U2") (pin "15") (pinfunction "IO9_15") (pintype "bidirectional"))
    )
    (net (code "18") (name "IO{slash}CHANGE") (class "Default")
      (node (ref "C10") (pin "1") (pinfunction "1_1") (pintype "passive"))
      (node (ref "CHANGE_BUTTON") (pin "3") (pinfunction "3_3") (pintype "passive"))
      (node (ref "CHANGE_BUTTON") (pin "4") (pinfunction "4_4") (pintype "passive"))
      (node (ref "R_CHANGE") (pin "2") (pinfunction "2_2") (pintype "passive"))
      (node (ref "U2") (pin "23") (pinfunction "IO15_23") (pintype "bidirectional"))
    )
    (net (code "19") (name "MISO") (class "Default")
      (node (ref "D12") (pin "2") (pinfunction "2_2") (pintype "passive"))
      (node (ref "J4") (pin "P7") (pinfunction "DAT0_P7") (pintype "bidirectional"))
      (node (ref "R8") (pin "1") (pinfunction "1_1") (pintype "passive"))
      (node (ref "TP6") (pin "TP") (pinfunction "TP_TP") (pintype "input"))
      (node (ref "U1") (pin "2") (pinfunction "DO(IO1)_2") (pintype "bidirectional"))
      (node (ref "U2") (pin "27") (pinfunction "IO2_27") (pintype "bidirectional"))
    )
    (net (code "20") (name "MOSI") (class "Default")
      (node (ref "D11") (pin "2") (pinfunction "2_2") (pintype "passive"))
      (node (ref "J1") (pin "14") (pinfunction "14_14") (pintype "bidirectional"))
      (node (ref "J4") (pin "P3") (pinfunction "CMD_P3") (pintype "bidirectional"))
      (node (ref "R7") (pin "1") (pinfunction "1_1") (pintype "passive"))
      (node (ref "TP7") (pin "TP") (pinfunction "TP_TP") (pintype "input"))
      (node (ref "U1") (pin "5") (pinfunction "DI(IO0)_5") (pintype "bidirectional"))
      (node (ref "U2") (pin "7") (pinfunction "IO7_7") (pintype "bidirectional"))
    )
    (net (code "21") (name "Net-(CHG_LED-PadC)") (class "Default")
      (node (ref "CHG_LED") (pin "C") (pinfunction "C_C") (pintype "passive"))
      (node (ref "R1_BAT") (pin "2") (pinfunction "2_2") (pintype "passive"))
    )
    (net (code "22") (name "Net-(D2-CATHODE)") (class "Default")
      (node (ref "C1_BAT1") (pin "1") (pinfunction "1_1") (pintype "passive"))
      (node (ref "D2") (pin "1") (pinfunction "CATHODE_1") (pintype "bidirectional"))
      (node (ref "IC4") (pin "1") (pinfunction "VIN_1") (pintype "bidirectional"))
      (node (ref "IC4") (pin "3") (pinfunction "CE_3") (pintype "bidirectional"))
      (node (ref "Q1") (pin "2") (pinfunction "S_2") (pintype "bidirectional"))
    )
    (net (code "23") (name "Net-(D3-A)") (class "Default")
      (node (ref "C4") (pin "1") (pinfunction "1_1") (pintype "passive"))
      (node (ref "D3") (pin "2") (pinfunction "A_2") (pintype "bidirectional"))
      (node (ref "D4") (pin "1") (pinfunction "K_1") (pintype "bidirectional"))
    )
    (net (code "24") (name "Net-(D7-CATHODE)") (class "Default")
      (node (ref "D7") (pin "1") (pinfunction "CATHODE_1") (pintype "bidirectional"))
      (node (ref "R_CAPACITOR") (pin "1") (pinfunction "1_1") (pintype "passive"))
    )
    (net (code "25") (name "Net-(EPD_C1-Pad1)") (class "Default")
      (node (ref "EPD_C1") (pin "1") (pinfunction "1_1") (pintype "passive"))
      (node (ref "J1") (pin "4") (pinfunction "4_4") (pintype "bidirectional"))
    )
    (net (code "26") (name "Net-(EPD_C2-Pad1)") (class "Default")
      (node (ref "EPD_C2") (pin "1") (pinfunction "1_1") (pintype "passive"))
      (node (ref "J1") (pin "5") (pinfunction "5_5") (pintype "bidirectional"))
    )
    (net (code "27") (name "Net-(EPD_C6-Pad1)") (class "Default")
      (node (ref "EPD_C6") (pin "1") (pinfunction "1_1") (pintype "passive"))
      (node (ref "J1") (pin "18") (pinfunction "18_18") (pintype "bidirectional"))
    )
    (net (code "28") (name "Net-(EPD_C7-Pad1)") (class "Default")
      (node (ref "EPD_C7") (pin "1") (pinfunction "1_1") (pintype "passive"))
      (node (ref "J1") (pin "19") (pinfunction "19_19") (pintype "bidirectional"))
    )
    (net (code "29") (name "Net-(EPD_C8-Pad1)") (class "Default")
      (node (ref "EPD_C8") (pin "1") (pinfunction "1_1") (pintype "passive"))
      (node (ref "J1") (pin "20") (pinfunction "20_20") (pintype "bidirectional"))
    )
    (net (code "30") (name "Net-(EPD_C10-Pad1)") (class "Default")
      (node (ref "EPD_C10") (pin "1") (pinfunction "1_1") (pintype "passive"))
      (node (ref "J1") (pin "22") (pinfunction "22_22") (pintype "bidirectional"))
    )
    (net (code "31") (name "Net-(EPD_C12-Pad1)") (class "Default")
      (node (ref "EPD_C12") (pin "1") (pinfunction "1_1") (pintype "passive"))
      (node (ref "J1") (pin "24") (pinfunction "24_24") (pintype "bidirectional"))
    )
    (net (code "32") (name "Net-(IC1-CT)") (class "Default")
      (node (ref "C_DELAY") (pin "1") (pinfunction "1_1") (pintype "passive"))
      (node (ref "IC1") (pin "5") (pinfunction "CT_5") (pintype "bidirectional"))
    )
    (net (code "33") (name "Net-(J2-PadA5)") (class "Default")
      (node (ref "J2") (pin "A5") (pinfunction "A5_A5") (pintype "bidirectional"))
      (node (ref "R2-USB1") (pin "2") (pinfunction "2_2") (pintype "passive"))
    )
    (net (code "34") (name "Net-(J2-PadB5)") (class "Default")
      (node (ref "J2") (pin "B5") (pinfunction "B5_B5") (pintype "bidirectional"))
      (node (ref "R2-USB") (pin "1") (pinfunction "1_1") (pintype "passive"))
    )
    (net (code "35") (name "Net-(MCP73831-PROG)") (class "Default")
      (node (ref "MCP73831") (pin "5") (pinfunction "PROG_5") (pintype "input"))
      (node (ref "R2_BAT") (pin "2") (pinfunction "2_2") (pintype "passive"))
    )
    (net (code "36") (name "Net-(MCP73831-STAT)") (class "Default")
      (node (ref "MCP73831") (pin "1") (pinfunction "STAT_1") (pintype "output"))
      (node (ref "R1_BAT") (pin "1") (pinfunction "1_1") (pintype "passive"))
    )
    (net (code "37") (name "PREVGH") (class "Default")
      (node (ref "D5") (pin "1") (pinfunction "K_1") (pintype "bidirectional"))
      (node (ref "EPD_C9") (pin "1") (pinfunction "1_1") (pintype "passive"))
      (node (ref "J1") (pin "21") (pinfunction "21_21") (pintype "bidirectional"))
    )
    (net (code "38") (name "PREVGL") (class "Default")
      (node (ref "D4") (pin "2") (pinfunction "A_2") (pintype "bidirectional"))
      (node (ref "EPD_C11") (pin "1") (pinfunction "1_1") (pintype "passive"))
      (node (ref "J1") (pin "23") (pinfunction "23_23") (pintype "bidirectional"))
    )
    (net (code "39") (name "RESE") (class "Default")
      (node (ref "J1") (pin "3") (pinfunction "3_3") (pintype "bidirectional"))
      (node (ref "Q3") (pin "2") (pinfunction "S_2") (pintype "bidirectional"))
      (node (ref "R3") (pin "1") (pinfunction "1_1") (pintype "passive"))
    )
    (net (code "40") (name "RESE'") (class "Default")
      (node (ref "R2") (pin "2") (pinfunction "2_2") (pintype "passive"))
      (node (ref "R3") (pin "2") (pinfunction "2_2") (pintype "passive"))
      (node (ref "SJ1") (pin "2") (pinfunction "2_2") (pintype "passive"))
    )
    (net (code "41") (name "RESET") (class "Default")
      (node (ref "C5") (pin "1") (pinfunction "1_1") (pintype "passive"))
      (node (ref "IC1") (pin "1") (pinfunction "VOUT_1") (pintype "bidirectional"))
      (node (ref "RESET_BUTTON") (pin "3") (pinfunction "3_3") (pintype "passive"))
      (node (ref "RESET_BUTTON") (pin "4") (pinfunction "4_4") (pintype "passive"))
      (node (ref "R_RESET") (pin "2") (pinfunction "2_2") (pintype "passive"))
      (node (ref "U2") (pin "3") (pinfunction "EN_3") (pintype "input"))
    )
    (net (code "42") (name "RTC_RST") (class "Default")
      (node (ref "U2") (pin "16") (pinfunction "IO18_16") (pintype "bidirectional"))
      (node (ref "U3") (pin "4") (pinfunction "~{RST}_4") (pintype "input"))
    )
    (net (code "43") (name "RX") (class "Default")
      (node (ref "TP2") (pin "TP") (pinfunction "TP_TP") (pintype "input"))
      (node (ref "U2") (pin "24") (pinfunction "RXD0/GPIO17_24") (pintype "bidirectional"))
    )
    (net (code "44") (name "SCK") (class "Default")
      (node (ref "D10") (pin "2") (pinfunction "2_2") (pintype "passive"))
      (node (ref "J1") (pin "13") (pinfunction "13_13") (pintype "bidirectional"))
      (node (ref "J4") (pin "P5") (pinfunction "CLK_P5") (pintype "bidirectional"))
      (node (ref "R6") (pin "1") (pinfunction "1_1") (pintype "passive"))
      (node (ref "TP8") (pin "TP") (pinfunction "TP_TP") (pintype "input"))
      (node (ref "U1") (pin "6") (pinfunction "CLK_6") (pintype "input"))
      (node (ref "U2") (pin "6") (pinfunction "IO6_6") (pintype "bidirectional"))
    )
    (net (code "45") (name "SCL") (class "Default")
      (node (ref "J3") (pin "4") (pinfunction "4_4") (pintype "passive"))
      (node (ref "R2_PINH") (pin "1") (pinfunction "1_1") (pintype "passive"))
      (node (ref "SENSOR2") (pin "4") (pinfunction "SCK_4") (pintype "input"))
      (node (ref "U2") (pin "20") (pinfunction "IO22_20") (pintype "bidirectional"))
      (node (ref "U3") (pin "16") (pinfunction "SCL_16") (pintype "input"))
      (node (ref "U4") (pin "7") (pinfunction "SCL_7") (pintype "input"))
    )
    (net (code "46") (name "SDA") (class "Default")
      (node (ref "J3") (pin "3") (pinfunction "3_3") (pintype "passive"))
      (node (ref "R1_PINH") (pin "1") (pinfunction "1_1") (pintype "passive"))
      (node (ref "SENSOR2") (pin "3") (pinfunction "SDI_3") (pintype "bidirectional"))
      (node (ref "U2") (pin "19") (pinfunction "IO21_19") (pintype "bidirectional"))
      (node (ref "U3") (pin "15") (pinfunction "SDA_15") (pintype "bidirectional"))
      (node (ref "U4") (pin "8") (pinfunction "SDA_8") (pintype "bidirectional"))
    )
    (net (code "47") (name "SRC") (class "Default")
      (node (ref "C4") (pin "2") (pinfunction "2_2") (pintype "passive"))
      (node (ref "D5") (pin "2") (pinfunction "A_2") (pintype "bidirectional"))
      (node (ref "L1") (pin "1") (pinfunction "1_1") (pintype "passive"))
      (node (ref "Q3") (pin "3") (pinfunction "D_3") (pintype "bidirectional"))
    )
    (net (code "48") (name "SS_SD") (class "Default")
      (node (ref "D8") (pin "2") (pinfunction "2_2") (pintype "passive"))
      (node (ref "J4") (pin "P2") (pinfunction "CD/DAT3_P2") (pintype "bidirectional"))
      (node (ref "R10") (pin "1") (pinfunction "1_1") (pintype "passive"))
      (node (ref "U2") (pin "4") (pinfunction "IO4_4") (pintype "bidirectional"))
    )
    (net (code "49") (name "TX") (class "Default")
      (node (ref "TP1") (pin "TP") (pinfunction "TP_TP") (pintype "input"))
      (node (ref "U2") (pin "25") (pinfunction "TXD0/GPIO16_25") (pintype "bidirectional"))
    )
    (net (code "50") (name "USB_D+") (class "Default")
      (node (ref "D1") (pin "1") (pinfunction "I/O1_1_1") (pintype "bidirectional"))
      (node (ref "U2") (pin "14") (pinfunction "IO13_14") (pintype "bidirectional"))
    )
    (net (code "51") (name "USB_D-") (class "Default")
      (node (ref "D1") (pin "3") (pinfunction "I/O2_1_3") (pintype "bidirectional"))
      (node (ref "U2") (pin "13") (pinfunction "IO12_13") (pintype "bidirectional"))
    )
    (net (code "52") (name "VBAT") (class "Default")
      (node (ref "C2_BAT") (pin "1") (pinfunction "1_1") (pintype "passive"))
      (node (ref "MCP73831") (pin "3") (pinfunction "VBAT_3") (pintype "power_in"))
      (node (ref "Q1") (pin "3") (pinfunction "D_3") (pintype "bidirectional"))
      (node (ref "TP3") (pin "TP") (pinfunction "TP_TP") (pintype "input"))
      (node (ref "U4") (pin "2") (pinfunction "CELL_2") (pintype "power_in"))
      (node (ref "U4") (pin "3") (pinfunction "VDD_3") (pintype "power_in"))
    )
    (net (code "53") (name "VBUS") (class "Default")
      (node (ref "C1_BAT") (pin "1") (pinfunction "1_1") (pintype "passive"))
      (node (ref "C4_USB") (pin "1") (pinfunction "1_1") (pintype "passive"))
      (node (ref "C5_USB") (pin "1") (pinfunction "1_1") (pintype "passive"))
      (node (ref "CHG_LED") (pin "A") (pinfunction "A_A") (pintype "passive"))
      (node (ref "D1") (pin "5") (pinfunction "VBUS_5") (pintype "bidirectional"))
      (node (ref "D2") (pin "2") (pinfunction "ANODE_2") (pintype "bidirectional"))
      (node (ref "MCP73831") (pin "4") (pinfunction "VIN_4") (pintype "power_in"))
      (node (ref "PFMF.050.1") (pin "2") (pinfunction "2_2") (pintype "passive"))
      (node (ref "Q1") (pin "1") (pinfunction "G_1") (pintype "bidirectional"))
      (node (ref "R1_PWRUSB") (pin "2") (pinfunction "2_2") (pintype "passive"))
      (node (ref "TP14") (pin "TP") (pinfunction "TP_TP") (pintype "input"))
    )
    (net (code "54") (name "VRTC") (class "Default")
      (node (ref "C10_SUPERCAP") (pin "2") (pinfunction "2_2") (pintype "passive"))
      (node (ref "C8") (pin "1") (pinfunction "1_1") (pintype "passive"))
      (node (ref "R_CAPACITOR") (pin "2") (pinfunction "2_2") (pintype "passive"))
      (node (ref "U3") (pin "14") (pinfunction "VBAT_14") (pintype "power_in"))
    )
    (net (code "55") (name "VUSB") (class "Default")
      (node (ref "J2") (pin "A4") (pinfunction "A4_A4") (pintype "bidirectional"))
      (node (ref "J2") (pin "A9") (pinfunction "A9_A9") (pintype "bidirectional"))
      (node (ref "J2") (pin "B4") (pinfunction "B4_B4") (pintype "bidirectional"))
      (node (ref "J2") (pin "B9") (pinfunction "B9_B9") (pintype "bidirectional"))
      (node (ref "PFMF.050.1") (pin "1") (pinfunction "1_1") (pintype "passive"))
    )
    (net (code "56") (name "unconnected-(IC1-NC-Pad4)") (class "Default")
      (node (ref "IC1") (pin "4") (pinfunction "NC_4") (pintype "no_connect"))
    )
    (net (code "57") (name "unconnected-(IC4-NC-Pad4)") (class "Default")
      (node (ref "IC4") (pin "4") (pinfunction "NC_4") (pintype "no_connect"))
    )
    (net (code "58") (name "unconnected-(J1-Pad1)") (class "Default")
      (node (ref "J1") (pin "1") (pinfunction "1_1") (pintype "bidirectional"))
    )
    (net (code "59") (name "unconnected-(J1-Pad6)") (class "Default")
      (node (ref "J1") (pin "6") (pinfunction "6_6") (pintype "bidirectional"))
    )
    (net (code "60") (name "unconnected-(J1-Pad7)") (class "Default")
      (node (ref "J1") (pin "7") (pinfunction "7_7") (pintype "bidirectional"))
    )
    (net (code "61") (name "unconnected-(J1-Pad8)") (class "Default")
      (node (ref "J1") (pin "8") (pinfunction "8_8") (pintype "bidirectional"))
    )
    (net (code "62") (name "unconnected-(J2-PadA8)") (class "Default")
      (node (ref "J2") (pin "A8") (pinfunction "A8_A8") (pintype "bidirectional"))
    )
    (net (code "63") (name "unconnected-(J2-PadB8)") (class "Default")
      (node (ref "J2") (pin "B8") (pinfunction "B8_B8") (pintype "bidirectional"))
    )
    (net (code "64") (name "unconnected-(J4-DAT1-PadP8)") (class "Default")
      (node (ref "J4") (pin "P8") (pinfunction "DAT1_P8") (pintype "bidirectional"))
    )
    (net (code "65") (name "unconnected-(J4-DAT2-PadP1)") (class "Default")
      (node (ref "J4") (pin "P1") (pinfunction "DAT2_P1") (pintype "bidirectional"))
    )
    (net (code "66") (name "unconnected-(J4-DETECTION_1-PadS1)") (class "Default")
      (node (ref "J4") (pin "S1") (pinfunction "DETECTION_1_S1") (pintype "bidirectional"))
    )
    (net (code "67") (name "unconnected-(J4-DETECTION_2-PadS2)") (class "Default")
      (node (ref "J4") (pin "S2") (pinfunction "DETECTION_2_S2") (pintype "bidirectional"))
    )
    (net (code "68") (name "unconnected-(U2-NC-Pad22)") (class "Default")
      (node (ref "U2") (pin "22") (pinfunction "NC_22") (pintype "no_connect"))
    )
    (net (code "69") (name "unconnected-(U4-~{ALERT}-Pad5)") (class "Default")
      (node (ref "U4") (pin "5") (pinfunction "~{ALERT}_5") (pintype "output"))
    )
  )
)
